# 5_-_MICROCONTROLLER.net
KiCad netlist of a schematic drawn in Altium Designer
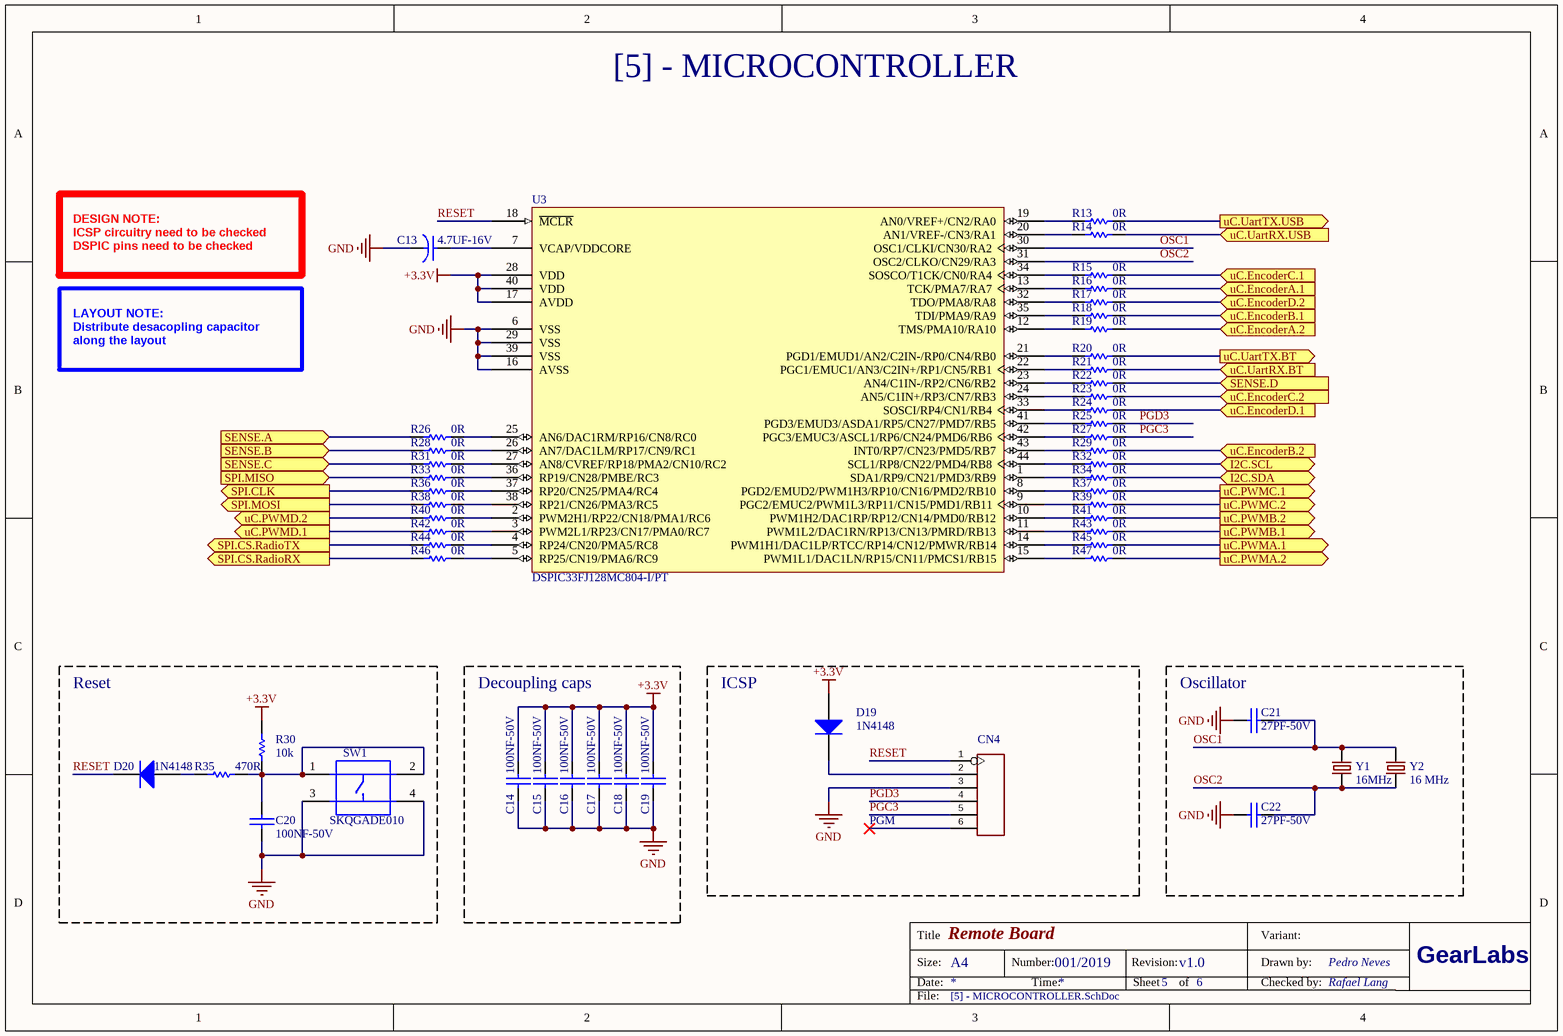
[diagram p0: [5] - MICROCONTROLLER.SchDoc]

(export (version "E")
  (design (tool "Eeschema 10.0.6"))
  (components
    (comp (ref "C13")
      (value "4.7UF-16V")
      (footprint "AVX-A")
      (fields (field (name "MPN") "TAJA475*016#NJ") (field (name "Comment") "302020006"))
      (libsource (lib "Seeed-Capacitor") (part "TANTALUM-SMD-4.7UF-16V(AVX-A)"))
    )
    (comp (ref "C14")
      (value "100NF-50V")
      (footprint "C0603")
      (fields (field (name "MPN") "CC0603KRX7R9BB104") (field (name "Comment") "302010138"))
      (libsource (lib "Seeed-Capacitor") (part "CERAMIC-100NF-50V-10%-X7R(0603)"))
    )
    (comp (ref "C15")
      (value "100NF-50V")
      (footprint "C0603")
      (fields (field (name "MPN") "CC0603KRX7R9BB104") (field (name "Comment") "302010138"))
      (libsource (lib "Seeed-Capacitor") (part "CERAMIC-100NF-50V-10%-X7R(0603)"))
    )
    (comp (ref "C16")
      (value "100NF-50V")
      (footprint "C0603")
      (fields (field (name "MPN") "CC0603KRX7R9BB104") (field (name "Comment") "302010138"))
      (libsource (lib "Seeed-Capacitor") (part "CERAMIC-100NF-50V-10%-X7R(0603)"))
    )
    (comp (ref "C17")
      (value "100NF-50V")
      (footprint "C0603")
      (fields (field (name "MPN") "CC0603KRX7R9BB104") (field (name "Comment") "302010138"))
      (libsource (lib "Seeed-Capacitor") (part "CERAMIC-100NF-50V-10%-X7R(0603)"))
    )
    (comp (ref "C18")
      (value "100NF-50V")
      (footprint "C0603")
      (fields (field (name "MPN") "CC0603KRX7R9BB104") (field (name "Comment") "302010138"))
      (libsource (lib "Seeed-Capacitor") (part "CERAMIC-100NF-50V-10%-X7R(0603)"))
    )
    (comp (ref "C19")
      (value "100NF-50V")
      (footprint "C0603")
      (fields (field (name "MPN") "CC0603KRX7R9BB104") (field (name "Comment") "302010138"))
      (libsource (lib "Seeed-Capacitor") (part "CERAMIC-100NF-50V-10%-X7R(0603)"))
    )
    (comp (ref "C20")
      (value "100NF-50V")
      (footprint "C0603")
      (fields (field (name "MPN") "CC0603KRX7R9BB104") (field (name "Comment") "302010138"))
      (libsource (lib "Seeed-Capacitor") (part "CERAMIC-100NF-50V-10%-X7R(0603)"))
    )
    (comp (ref "C21")
      (value "27PF-50V")
      (footprint "C0603")
      (fields (field (name "MPN") "CC0603JRNPO9BN270") (field (name "Comment") "302010142"))
      (libsource (lib "Seeed-Capacitor") (part "CERAMIC-27PF-50V-5%-NPO(0603)"))
    )
    (comp (ref "C22")
      (value "27PF-50V")
      (footprint "C0603")
      (fields (field (name "MPN") "CC0603JRNPO9BN270") (field (name "Comment") "302010142"))
      (libsource (lib "Seeed-Capacitor") (part "CERAMIC-27PF-50V-5%-NPO(0603)"))
    )
    (comp (ref "CN4")
      (value "320030060")
      (footprint "H6-2.54")
      (fields (field (name "MPN") "F185-1106A1BSYC1"))
      (libsource (lib "Seeed-Connector") (part "DIP-BLACK-FEMALE-HEADER-VERT(6P-2.54)"))
    )
    (comp (ref "D19")
      (value "304040016")
      (footprint "LL-34")
      (fields (field (name "MPN") "1N4148"))
      (libsource (lib "Seeed-Diode") (part "SMD-DIODE-SWITCH-1N4148(LL-34)"))
    )
    (comp (ref "D20")
      (value "304040016")
      (footprint "LL-34")
      (fields (field (name "MPN") "1N4148"))
      (libsource (lib "Seeed-Diode") (part "SMD-DIODE-SWITCH-1N4148(LL-34)"))
    )
    (comp (ref "R13")
      (value "0R")
      (footprint "R0603")
      (fields (field (name "MPN") "RC0603JR-070RL") (field (name "Comment") "301010292"))
      (libsource (lib "Seeed-Resistor") (part "SMD-RES-0R-5%-1/10W(0603)"))
    )
    (comp (ref "R14")
      (value "0R")
      (footprint "R0603")
      (fields (field (name "MPN") "RC0603JR-070RL") (field (name "Comment") "301010292"))
      (libsource (lib "Seeed-Resistor") (part "SMD-RES-0R-5%-1/10W(0603)"))
    )
    (comp (ref "R15")
      (value "0R")
      (footprint "R0603")
      (fields (field (name "MPN") "RC0603JR-070RL") (field (name "Comment") "301010292"))
      (libsource (lib "Seeed-Resistor") (part "SMD-RES-0R-5%-1/10W(0603)"))
    )
    (comp (ref "R16")
      (value "0R")
      (footprint "R0603")
      (fields (field (name "MPN") "RC0603JR-070RL") (field (name "Comment") "301010292"))
      (libsource (lib "Seeed-Resistor") (part "SMD-RES-0R-5%-1/10W(0603)"))
    )
    (comp (ref "R17")
      (value "0R")
      (footprint "R0603")
      (fields (field (name "MPN") "RC0603JR-070RL") (field (name "Comment") "301010292"))
      (libsource (lib "Seeed-Resistor") (part "SMD-RES-0R-5%-1/10W(0603)"))
    )
    (comp (ref "R18")
      (value "0R")
      (footprint "R0603")
      (fields (field (name "MPN") "RC0603JR-070RL") (field (name "Comment") "301010292"))
      (libsource (lib "Seeed-Resistor") (part "SMD-RES-0R-5%-1/10W(0603)"))
    )
    (comp (ref "R19")
      (value "0R")
      (footprint "R0603")
      (fields (field (name "MPN") "RC0603JR-070RL") (field (name "Comment") "301010292"))
      (libsource (lib "Seeed-Resistor") (part "SMD-RES-0R-5%-1/10W(0603)"))
    )
    (comp (ref "R20")
      (value "0R")
      (footprint "R0603")
      (fields (field (name "MPN") "RC0603JR-070RL") (field (name "Comment") "301010292"))
      (libsource (lib "Seeed-Resistor") (part "SMD-RES-0R-5%-1/10W(0603)"))
    )
    (comp (ref "R21")
      (value "0R")
      (footprint "R0603")
      (fields (field (name "MPN") "RC0603JR-070RL") (field (name "Comment") "301010292"))
      (libsource (lib "Seeed-Resistor") (part "SMD-RES-0R-5%-1/10W(0603)"))
    )
    (comp (ref "R22")
      (value "0R")
      (footprint "R0603")
      (fields (field (name "MPN") "RC0603JR-070RL") (field (name "Comment") "301010292"))
      (libsource (lib "Seeed-Resistor") (part "SMD-RES-0R-5%-1/10W(0603)"))
    )
    (comp (ref "R23")
      (value "0R")
      (footprint "R0603")
      (fields (field (name "MPN") "RC0603JR-070RL") (field (name "Comment") "301010292"))
      (libsource (lib "Seeed-Resistor") (part "SMD-RES-0R-5%-1/10W(0603)"))
    )
    (comp (ref "R24")
      (value "0R")
      (footprint "R0603")
      (fields (field (name "MPN") "RC0603JR-070RL") (field (name "Comment") "301010292"))
      (libsource (lib "Seeed-Resistor") (part "SMD-RES-0R-5%-1/10W(0603)"))
    )
    (comp (ref "R25")
      (value "0R")
      (footprint "R0603")
      (fields (field (name "MPN") "RC0603JR-070RL") (field (name "Comment") "301010292"))
      (libsource (lib "Seeed-Resistor") (part "SMD-RES-0R-5%-1/10W(0603)"))
    )
    (comp (ref "R26")
      (value "0R")
      (footprint "R0603")
      (fields (field (name "MPN") "RC0603JR-070RL") (field (name "Comment") "301010292"))
      (libsource (lib "Seeed-Resistor") (part "SMD-RES-0R-5%-1/10W(0603)"))
    )
    (comp (ref "R27")
      (value "0R")
      (footprint "R0603")
      (fields (field (name "MPN") "RC0603JR-070RL") (field (name "Comment") "301010292"))
      (libsource (lib "Seeed-Resistor") (part "SMD-RES-0R-5%-1/10W(0603)"))
    )
    (comp (ref "R28")
      (value "0R")
      (footprint "R0603")
      (fields (field (name "MPN") "RC0603JR-070RL") (field (name "Comment") "301010292"))
      (libsource (lib "Seeed-Resistor") (part "SMD-RES-0R-5%-1/10W(0603)"))
    )
    (comp (ref "R29")
      (value "0R")
      (footprint "R0603")
      (fields (field (name "MPN") "RC0603JR-070RL") (field (name "Comment") "301010292"))
      (libsource (lib "Seeed-Resistor") (part "SMD-RES-0R-5%-1/10W(0603)"))
    )
    (comp (ref "R30")
      (value "10k")
      (footprint "R0603")
      (fields (field (name "MPN") "RC0603FR-0710KL") (field (name "Comment") "301010299"))
      (libsource (lib "Seeed-Resistor") (part "SMD-RES-10K-1%-1/10W(0603)"))
    )
    (comp (ref "R31")
      (value "0R")
      (footprint "R0603")
      (fields (field (name "MPN") "RC0603JR-070RL") (field (name "Comment") "301010292"))
      (libsource (lib "Seeed-Resistor") (part "SMD-RES-0R-5%-1/10W(0603)"))
    )
    (comp (ref "R32")
      (value "0R")
      (footprint "R0603")
      (fields (field (name "MPN") "RC0603JR-070RL") (field (name "Comment") "301010292"))
      (libsource (lib "Seeed-Resistor") (part "SMD-RES-0R-5%-1/10W(0603)"))
    )
    (comp (ref "R33")
      (value "0R")
      (footprint "R0603")
      (fields (field (name "MPN") "RC0603JR-070RL") (field (name "Comment") "301010292"))
      (libsource (lib "Seeed-Resistor") (part "SMD-RES-0R-5%-1/10W(0603)"))
    )
    (comp (ref "R34")
      (value "0R")
      (footprint "R0603")
      (fields (field (name "MPN") "RC0603JR-070RL") (field (name "Comment") "301010292"))
      (libsource (lib "Seeed-Resistor") (part "SMD-RES-0R-5%-1/10W(0603)"))
    )
    (comp (ref "R35")
      (value "470R")
      (footprint "R0603")
      (fields (field (name "MPN") "RC0603JR-07470RL") (field (name "Comment") "301010088"))
      (libsource (lib "Seeed-Resistor") (part "SMD-RES-470R-5%-1/10W(0603)"))
    )
    (comp (ref "R36")
      (value "0R")
      (footprint "R0603")
      (fields (field (name "MPN") "RC0603JR-070RL") (field (name "Comment") "301010292"))
      (libsource (lib "Seeed-Resistor") (part "SMD-RES-0R-5%-1/10W(0603)"))
    )
    (comp (ref "R37")
      (value "0R")
      (footprint "R0603")
      (fields (field (name "MPN") "RC0603JR-070RL") (field (name "Comment") "301010292"))
      (libsource (lib "Seeed-Resistor") (part "SMD-RES-0R-5%-1/10W(0603)"))
    )
    (comp (ref "R38")
      (value "0R")
      (footprint "R0603")
      (fields (field (name "MPN") "RC0603JR-070RL") (field (name "Comment") "301010292"))
      (libsource (lib "Seeed-Resistor") (part "SMD-RES-0R-5%-1/10W(0603)"))
    )
    (comp (ref "R39")
      (value "0R")
      (footprint "R0603")
      (fields (field (name "MPN") "RC0603JR-070RL") (field (name "Comment") "301010292"))
      (libsource (lib "Seeed-Resistor") (part "SMD-RES-0R-5%-1/10W(0603)"))
    )
    (comp (ref "R40")
      (value "0R")
      (footprint "R0603")
      (fields (field (name "MPN") "RC0603JR-070RL") (field (name "Comment") "301010292"))
      (libsource (lib "Seeed-Resistor") (part "SMD-RES-0R-5%-1/10W(0603)"))
    )
    (comp (ref "R41")
      (value "0R")
      (footprint "R0603")
      (fields (field (name "MPN") "RC0603JR-070RL") (field (name "Comment") "301010292"))
      (libsource (lib "Seeed-Resistor") (part "SMD-RES-0R-5%-1/10W(0603)"))
    )
    (comp (ref "R42")
      (value "0R")
      (footprint "R0603")
      (fields (field (name "MPN") "RC0603JR-070RL") (field (name "Comment") "301010292"))
      (libsource (lib "Seeed-Resistor") (part "SMD-RES-0R-5%-1/10W(0603)"))
    )
    (comp (ref "R43")
      (value "0R")
      (footprint "R0603")
      (fields (field (name "MPN") "RC0603JR-070RL") (field (name "Comment") "301010292"))
      (libsource (lib "Seeed-Resistor") (part "SMD-RES-0R-5%-1/10W(0603)"))
    )
    (comp (ref "R44")
      (value "0R")
      (footprint "R0603")
      (fields (field (name "MPN") "RC0603JR-070RL") (field (name "Comment") "301010292"))
      (libsource (lib "Seeed-Resistor") (part "SMD-RES-0R-5%-1/10W(0603)"))
    )
    (comp (ref "R45")
      (value "0R")
      (footprint "R0603")
      (fields (field (name "MPN") "RC0603JR-070RL") (field (name "Comment") "301010292"))
      (libsource (lib "Seeed-Resistor") (part "SMD-RES-0R-5%-1/10W(0603)"))
    )
    (comp (ref "R46")
      (value "0R")
      (footprint "R0603")
      (fields (field (name "MPN") "RC0603JR-070RL") (field (name "Comment") "301010292"))
      (libsource (lib "Seeed-Resistor") (part "SMD-RES-0R-5%-1/10W(0603)"))
    )
    (comp (ref "R47")
      (value "0R")
      (footprint "R0603")
      (fields (field (name "MPN") "RC0603JR-070RL") (field (name "Comment") "301010292"))
      (libsource (lib "Seeed-Resistor") (part "SMD-RES-0R-5%-1/10W(0603)"))
    )
    (comp (ref "SW1")
      (value "311020017")
      (footprint "SW4-SMD-5.2X5.2X1.5MM")
      (fields (field (name "MPN") "SKQGADE010"))
      (libsource (lib "Seeed-Switch") (part "SMD-BUTTON(4P-5.2X5.2X1.5MM-SKQGADE010)-SKQGADE010"))
    )
    (comp (ref "U3")
      (value "DSPIC33FJ128MC804-I/PT")
      (footprint "TQFP-44")
      (description "High-Performance 16-bit Digital Signal Controller, 128 KB Flash, 16 KB RAM, 44-Pin TQFP")
      (libsource (lib "Circuitos Integrados") (part "DSPIC33FJ128MC804-I/PT"))
    )
    (comp (ref "Y1")
      (value "16MHz")
      (footprint "X2-SMD-5.0X3.2X1.3MM")
      (fields (field (name "MPN") "X053201602002") (field (name "Comment") "306010054"))
      (libsource (lib "Seeed-Crystal Oscillator") (part "SMD-CRYSTAL-16MHZ-8PF-20PPM-40R(2P-5.0X3.2MM)"))
    )
    (comp (ref "Y2")
      (value "16 MHz")
      (footprint "HC49US")
      (fields (field (name "MPN") "HC-49US    16.000MHz") (field (name "Comment") "306010014"))
      (libsource (lib "Seeed-Crystal Oscillator") (part "DIP-CRYSTAL-16MHZ-18PF-30PPM-40R(HC49US)"))
    )
  )
  (nets
    (net (code "1") (name "+3.3V") (class "Default")
      (node (ref "C14") (pin "1") (pinfunction "1_1") (pintype "passive"))
      (node (ref "C15") (pin "1") (pinfunction "1_1") (pintype "passive"))
      (node (ref "C16") (pin "1") (pinfunction "1_1") (pintype "passive"))
      (node (ref "C17") (pin "1") (pinfunction "1_1") (pintype "passive"))
      (node (ref "C18") (pin "1") (pinfunction "1_1") (pintype "passive"))
      (node (ref "C19") (pin "1") (pinfunction "1_1") (pintype "passive"))
      (node (ref "D19") (pin "A") (pinfunction "+_A") (pintype "passive"))
      (node (ref "R30") (pin "2") (pinfunction "2_2") (pintype "passive"))
      (node (ref "U3") (pin "17") (pinfunction "AVDD_17") (pintype "power_in"))
      (node (ref "U3") (pin "28") (pinfunction "VDD_28") (pintype "power_in"))
      (node (ref "U3") (pin "40") (pinfunction "VDD_40") (pintype "power_in"))
    )
    (net (code "2") (name "/I2C.SCL") (class "Default")
      (node (ref "R32") (pin "2") (pinfunction "2_2") (pintype "passive"))
    )
    (net (code "3") (name "/I2C.SDA") (class "Default")
      (node (ref "R34") (pin "2") (pinfunction "2_2") (pintype "passive"))
    )
    (net (code "4") (name "/OSC1") (class "Default")
      (node (ref "C21") (pin "1") (pinfunction "1_1") (pintype "passive"))
      (node (ref "U3") (pin "30") (pinfunction "OSC1/CLKI/CN30/RA2_30") (pintype "bidirectional"))
      (node (ref "Y1") (pin "2") (pinfunction "2_2") (pintype "passive"))
      (node (ref "Y2") (pin "2") (pinfunction "2_2") (pintype "passive"))
    )
    (net (code "5") (name "/OSC2") (class "Default")
      (node (ref "C22") (pin "1") (pinfunction "1_1") (pintype "passive"))
      (node (ref "U3") (pin "31") (pinfunction "OSC2/CLKO/CN29/RA3_31") (pintype "bidirectional"))
      (node (ref "Y1") (pin "1") (pinfunction "1_1") (pintype "passive"))
      (node (ref "Y2") (pin "1") (pinfunction "1_1") (pintype "passive"))
    )
    (net (code "6") (name "/PGC3") (class "Default")
      (node (ref "CN4") (pin "5") (pinfunction "5_5") (pintype "passive"))
      (node (ref "R27") (pin "2") (pinfunction "2_2") (pintype "passive"))
    )
    (net (code "7") (name "/PGD3") (class "Default")
      (node (ref "CN4") (pin "4") (pinfunction "4_4") (pintype "passive"))
      (node (ref "R25") (pin "2") (pinfunction "2_2") (pintype "passive"))
    )
    (net (code "8") (name "/RESET") (class "Default")
      (node (ref "CN4") (pin "1") (pinfunction "1_1") (pintype "passive"))
      (node (ref "D20") (pin "C") (pinfunction "-_C") (pintype "passive"))
      (node (ref "U3") (pin "18") (pinfunction "~{MCLR}_18") (pintype "input"))
    )
    (net (code "9") (name "/SENSE.A") (class "Default")
      (node (ref "R26") (pin "1") (pinfunction "1_1") (pintype "passive"))
    )
    (net (code "10") (name "/SENSE.B") (class "Default")
      (node (ref "R28") (pin "1") (pinfunction "1_1") (pintype "passive"))
    )
    (net (code "11") (name "/SENSE.C") (class "Default")
      (node (ref "R31") (pin "1") (pinfunction "1_1") (pintype "passive"))
    )
    (net (code "12") (name "/SENSE.D") (class "Default")
      (node (ref "R22") (pin "2") (pinfunction "2_2") (pintype "passive"))
    )
    (net (code "13") (name "/SPI.CLK") (class "Default")
      (node (ref "R36") (pin "1") (pinfunction "1_1") (pintype "passive"))
    )
    (net (code "14") (name "/SPI.CS.RadioRX") (class "Default")
      (node (ref "R46") (pin "1") (pinfunction "1_1") (pintype "passive"))
    )
    (net (code "15") (name "/SPI.CS.RadioTX") (class "Default")
      (node (ref "R44") (pin "1") (pinfunction "1_1") (pintype "passive"))
    )
    (net (code "16") (name "/SPI.MISO") (class "Default")
      (node (ref "R33") (pin "1") (pinfunction "1_1") (pintype "passive"))
    )
    (net (code "17") (name "/SPI.MOSI") (class "Default")
      (node (ref "R38") (pin "1") (pinfunction "1_1") (pintype "passive"))
    )
    (net (code "18") (name "/uC.EncoderA.1") (class "Default")
      (node (ref "R16") (pin "2") (pinfunction "2_2") (pintype "passive"))
    )
    (net (code "19") (name "/uC.EncoderA.2") (class "Default")
      (node (ref "R19") (pin "2") (pinfunction "2_2") (pintype "passive"))
    )
    (net (code "20") (name "/uC.EncoderB.1") (class "Default")
      (node (ref "R18") (pin "2") (pinfunction "2_2") (pintype "passive"))
    )
    (net (code "21") (name "/uC.EncoderB.2") (class "Default")
      (node (ref "R29") (pin "2") (pinfunction "2_2") (pintype "passive"))
    )
    (net (code "22") (name "/uC.EncoderC.1") (class "Default")
      (node (ref "R15") (pin "2") (pinfunction "2_2") (pintype "passive"))
    )
    (net (code "23") (name "/uC.EncoderC.2") (class "Default")
      (node (ref "R23") (pin "2") (pinfunction "2_2") (pintype "passive"))
    )
    (net (code "24") (name "/uC.EncoderD.1") (class "Default")
      (node (ref "R24") (pin "2") (pinfunction "2_2") (pintype "passive"))
    )
    (net (code "25") (name "/uC.EncoderD.2") (class "Default")
      (node (ref "R17") (pin "2") (pinfunction "2_2") (pintype "passive"))
    )
    (net (code "26") (name "/uC.PWMA.1") (class "Default")
      (node (ref "R45") (pin "2") (pinfunction "2_2") (pintype "passive"))
    )
    (net (code "27") (name "/uC.PWMA.2") (class "Default")
      (node (ref "R47") (pin "2") (pinfunction "2_2") (pintype "passive"))
    )
    (net (code "28") (name "/uC.PWMB.1") (class "Default")
      (node (ref "R43") (pin "2") (pinfunction "2_2") (pintype "passive"))
    )
    (net (code "29") (name "/uC.PWMB.2") (class "Default")
      (node (ref "R41") (pin "2") (pinfunction "2_2") (pintype "passive"))
    )
    (net (code "30") (name "/uC.PWMC.1") (class "Default")
      (node (ref "R37") (pin "2") (pinfunction "2_2") (pintype "passive"))
    )
    (net (code "31") (name "/uC.PWMC.2") (class "Default")
      (node (ref "R39") (pin "2") (pinfunction "2_2") (pintype "passive"))
    )
    (net (code "32") (name "/uC.PWMD.1") (class "Default")
      (node (ref "R42") (pin "1") (pinfunction "1_1") (pintype "passive"))
    )
    (net (code "33") (name "/uC.PWMD.2") (class "Default")
      (node (ref "R40") (pin "1") (pinfunction "1_1") (pintype "passive"))
    )
    (net (code "34") (name "/uC.UartRX.BT") (class "Default")
      (node (ref "R21") (pin "2") (pinfunction "2_2") (pintype "passive"))
    )
    (net (code "35") (name "/uC.UartRX.USB") (class "Default")
      (node (ref "R14") (pin "2") (pinfunction "2_2") (pintype "passive"))
    )
    (net (code "36") (name "/uC.UartTX.BT") (class "Default")
      (node (ref "R20") (pin "2") (pinfunction "2_2") (pintype "passive"))
    )
    (net (code "37") (name "/uC.UartTX.USB") (class "Default")
      (node (ref "R13") (pin "2") (pinfunction "2_2") (pintype "passive"))
    )
    (net (code "38") (name "GND") (class "Default")
      (node (ref "C13") (pin "-") (pinfunction "-_-") (pintype "passive"))
      (node (ref "C14") (pin "2") (pinfunction "2_2") (pintype "passive"))
      (node (ref "C15") (pin "2") (pinfunction "2_2") (pintype "passive"))
      (node (ref "C16") (pin "2") (pinfunction "2_2") (pintype "passive"))
      (node (ref "C17") (pin "2") (pinfunction "2_2") (pintype "passive"))
      (node (ref "C18") (pin "2") (pinfunction "2_2") (pintype "passive"))
      (node (ref "C19") (pin "2") (pinfunction "2_2") (pintype "passive"))
      (node (ref "C20") (pin "2") (pinfunction "2_2") (pintype "passive"))
      (node (ref "C21") (pin "2") (pinfunction "2_2") (pintype "passive"))
      (node (ref "C22") (pin "2") (pinfunction "2_2") (pintype "passive"))
      (node (ref "CN4") (pin "3") (pinfunction "3_3") (pintype "passive"))
      (node (ref "SW1") (pin "3") (pinfunction "B0_3") (pintype "passive"))
      (node (ref "SW1") (pin "4") (pinfunction "B1_4") (pintype "passive"))
      (node (ref "U3") (pin "16") (pinfunction "AVSS_16") (pintype "power_in"))
      (node (ref "U3") (pin "29") (pinfunction "VSS_29") (pintype "power_in"))
      (node (ref "U3") (pin "39") (pinfunction "VSS_39") (pintype "power_in"))
      (node (ref "U3") (pin "6") (pinfunction "VSS_6") (pintype "power_in"))
    )
    (net (code "39") (name "Net-(D19--)") (class "Default")
      (node (ref "CN4") (pin "2") (pinfunction "2_2") (pintype "passive"))
      (node (ref "D19") (pin "C") (pinfunction "-_C") (pintype "passive"))
    )
    (net (code "40") (name "Net-(D20-+)") (class "Default")
      (node (ref "D20") (pin "A") (pinfunction "+_A") (pintype "passive"))
      (node (ref "R35") (pin "1") (pinfunction "1_1") (pintype "passive"))
    )
    (net (code "41") (name "Net-(SW1-A0)") (class "Default")
      (node (ref "C20") (pin "1") (pinfunction "1_1") (pintype "passive"))
      (node (ref "R30") (pin "1") (pinfunction "1_1") (pintype "passive"))
      (node (ref "R35") (pin "2") (pinfunction "2_2") (pintype "passive"))
      (node (ref "SW1") (pin "1") (pinfunction "A0_1") (pintype "passive"))
      (node (ref "SW1") (pin "2") (pinfunction "A1_2") (pintype "passive"))
    )
    (net (code "42") (name "Net-(U3-AN0{slash}VREF+{slash}CN2{slash}RA0)") (class "Default")
      (node (ref "R13") (pin "1") (pinfunction "1_1") (pintype "passive"))
      (node (ref "U3") (pin "19") (pinfunction "AN0/VREF+/CN2/RA0_19") (pintype "bidirectional"))
    )
    (net (code "43") (name "Net-(U3-AN1{slash}VREF-{slash}CN3{slash}RA1)") (class "Default")
      (node (ref "R14") (pin "1") (pinfunction "1_1") (pintype "passive"))
      (node (ref "U3") (pin "20") (pinfunction "AN1/VREF-/CN3/RA1_20") (pintype "bidirectional"))
    )
    (net (code "44") (name "Net-(U3-AN4{slash}C1IN-{slash}RP2{slash}CN6{slash}RB2)") (class "Default")
      (node (ref "R22") (pin "1") (pinfunction "1_1") (pintype "passive"))
      (node (ref "U3") (pin "23") (pinfunction "AN4/C1IN-/RP2/CN6/RB2_23") (pintype "bidirectional"))
    )
    (net (code "45") (name "Net-(U3-AN5{slash}C1IN+{slash}RP3{slash}CN7{slash}RB3)") (class "Default")
      (node (ref "R23") (pin "1") (pinfunction "1_1") (pintype "passive"))
      (node (ref "U3") (pin "24") (pinfunction "AN5/C1IN+/RP3/CN7/RB3_24") (pintype "bidirectional"))
    )
    (net (code "46") (name "Net-(U3-AN6{slash}DAC1RM{slash}RP16{slash}CN8{slash}RC0)") (class "Default")
      (node (ref "R26") (pin "2") (pinfunction "2_2") (pintype "passive"))
      (node (ref "U3") (pin "25") (pinfunction "AN6/DAC1RM/RP16/CN8/RC0_25") (pintype "bidirectional"))
    )
    (net (code "47") (name "Net-(U3-AN7{slash}DAC1LM{slash}RP17{slash}CN9{slash}RC1)") (class "Default")
      (node (ref "R28") (pin "2") (pinfunction "2_2") (pintype "passive"))
      (node (ref "U3") (pin "26") (pinfunction "AN7/DAC1LM/RP17/CN9/RC1_26") (pintype "bidirectional"))
    )
    (net (code "48") (name "Net-(U3-AN8{slash}CVREF{slash}RP18{slash}PMA2{slash}CN10{slash}RC2)") (class "Default")
      (node (ref "R31") (pin "2") (pinfunction "2_2") (pintype "passive"))
      (node (ref "U3") (pin "27") (pinfunction "AN8/CVREF/RP18/PMA2/CN10/RC2_27") (pintype "bidirectional"))
    )
    (net (code "49") (name "Net-(U3-INT0{slash}RP7{slash}CN23{slash}PMD5{slash}RB7)") (class "Default")
      (node (ref "R29") (pin "1") (pinfunction "1_1") (pintype "passive"))
      (node (ref "U3") (pin "43") (pinfunction "INT0/RP7/CN23/PMD5/RB7_43") (pintype "bidirectional"))
    )
    (net (code "50") (name "Net-(U3-PGC1{slash}EMUC1{slash}AN3{slash}C2IN+{slash}RP1{slash}CN5{slash}RB1)") (class "Default")
      (node (ref "R21") (pin "1") (pinfunction "1_1") (pintype "passive"))
      (node (ref "U3") (pin "22") (pinfunction "PGC1/EMUC1/AN3/C2IN+/RP1/CN5/RB1_22") (pintype "bidirectional"))
    )
    (net (code "51") (name "Net-(U3-PGC2{slash}EMUC2{slash}PWM1L3{slash}RP11{slash}CN15{slash}PMD1{slash}RB11)") (class "Default")
      (node (ref "R39") (pin "1") (pinfunction "1_1") (pintype "passive"))
      (node (ref "U3") (pin "9") (pinfunction "PGC2/EMUC2/PWM1L3/RP11/CN15/PMD1/RB11_9") (pintype "bidirectional"))
    )
    (net (code "52") (name "Net-(U3-PGC3{slash}EMUC3{slash}ASCL1{slash}RP6{slash}CN24{slash}PMD6{slash}RB6)") (class "Default")
      (node (ref "R27") (pin "1") (pinfunction "1_1") (pintype "passive"))
      (node (ref "U3") (pin "42") (pinfunction "PGC3/EMUC3/ASCL1/RP6/CN24/PMD6/RB6_42") (pintype "bidirectional"))
    )
    (net (code "53") (name "Net-(U3-PGD1{slash}EMUD1{slash}AN2{slash}C2IN-{slash}RP0{slash}CN4{slash}RB0)") (class "Default")
      (node (ref "R20") (pin "1") (pinfunction "1_1") (pintype "passive"))
      (node (ref "U3") (pin "21") (pinfunction "PGD1/EMUD1/AN2/C2IN-/RP0/CN4/RB0_21") (pintype "bidirectional"))
    )
    (net (code "54") (name "Net-(U3-PGD2{slash}EMUD2{slash}PWM1H3{slash}RP10{slash}CN16{slash}PMD2{slash}RB10)") (class "Default")
      (node (ref "R37") (pin "1") (pinfunction "1_1") (pintype "passive"))
      (node (ref "U3") (pin "8") (pinfunction "PGD2/EMUD2/PWM1H3/RP10/CN16/PMD2/RB10_8") (pintype "bidirectional"))
    )
    (net (code "55") (name "Net-(U3-PGD3{slash}EMUD3{slash}ASDA1{slash}RP5{slash}CN27{slash}PMD7{slash}RB5)") (class "Default")
      (node (ref "R25") (pin "1") (pinfunction "1_1") (pintype "passive"))
      (node (ref "U3") (pin "41") (pinfunction "PGD3/EMUD3/ASDA1/RP5/CN27/PMD7/RB5_41") (pintype "bidirectional"))
    )
    (net (code "56") (name "Net-(U3-PWM1H1{slash}DAC1LP{slash}RTCC{slash}RP14{slash}CN12{slash}PMWR{slash}RB14)") (class "Default")
      (node (ref "R45") (pin "1") (pinfunction "1_1") (pintype "passive"))
      (node (ref "U3") (pin "14") (pinfunction "PWM1H1/DAC1LP/RTCC/RP14/CN12/PMWR/RB14_14") (pintype "bidirectional"))
    )
    (net (code "57") (name "Net-(U3-PWM1H2{slash}DAC1RP{slash}RP12{slash}CN14{slash}PMD0{slash}RB12)") (class "Default")
      (node (ref "R41") (pin "1") (pinfunction "1_1") (pintype "passive"))
      (node (ref "U3") (pin "10") (pinfunction "PWM1H2/DAC1RP/RP12/CN14/PMD0/RB12_10") (pintype "bidirectional"))
    )
    (net (code "58") (name "Net-(U3-PWM1L1{slash}DAC1LN{slash}RP15{slash}CN11{slash}PMCS1{slash}RB15)") (class "Default")
      (node (ref "R47") (pin "1") (pinfunction "1_1") (pintype "passive"))
      (node (ref "U3") (pin "15") (pinfunction "PWM1L1/DAC1LN/RP15/CN11/PMCS1/RB15_15") (pintype "bidirectional"))
    )
    (net (code "59") (name "Net-(U3-PWM1L2{slash}DAC1RN{slash}RP13{slash}CN13{slash}PMRD{slash}RB13)") (class "Default")
      (node (ref "R43") (pin "1") (pinfunction "1_1") (pintype "passive"))
      (node (ref "U3") (pin "11") (pinfunction "PWM1L2/DAC1RN/RP13/CN13/PMRD/RB13_11") (pintype "bidirectional"))
    )
    (net (code "60") (name "Net-(U3-PWM2H1{slash}RP22{slash}CN18{slash}PMA1{slash}RC6)") (class "Default")
      (node (ref "R40") (pin "2") (pinfunction "2_2") (pintype "passive"))
      (node (ref "U3") (pin "2") (pinfunction "PWM2H1/RP22/CN18/PMA1/RC6_2") (pintype "bidirectional"))
    )
    (net (code "61") (name "Net-(U3-PWM2L1{slash}RP23{slash}CN17{slash}PMA0{slash}RC7)") (class "Default")
      (node (ref "R42") (pin "2") (pinfunction "2_2") (pintype "passive"))
      (node (ref "U3") (pin "3") (pinfunction "PWM2L1/RP23/CN17/PMA0/RC7_3") (pintype "bidirectional"))
    )
    (net (code "62") (name "Net-(U3-RP19{slash}CN28{slash}PMBE{slash}RC3)") (class "Default")
      (node (ref "R33") (pin "2") (pinfunction "2_2") (pintype "passive"))
      (node (ref "U3") (pin "36") (pinfunction "RP19/CN28/PMBE/RC3_36") (pintype "bidirectional"))
    )
    (net (code "63") (name "Net-(U3-RP20{slash}CN25{slash}PMA4{slash}RC4)") (class "Default")
      (node (ref "R36") (pin "2") (pinfunction "2_2") (pintype "passive"))
      (node (ref "U3") (pin "37") (pinfunction "RP20/CN25/PMA4/RC4_37") (pintype "bidirectional"))
    )
    (net (code "64") (name "Net-(U3-RP21{slash}CN26{slash}PMA3{slash}RC5)") (class "Default")
      (node (ref "R38") (pin "2") (pinfunction "2_2") (pintype "passive"))
      (node (ref "U3") (pin "38") (pinfunction "RP21/CN26/PMA3/RC5_38") (pintype "bidirectional"))
    )
    (net (code "65") (name "Net-(U3-RP24{slash}CN20{slash}PMA5{slash}RC8)") (class "Default")
      (node (ref "R44") (pin "2") (pinfunction "2_2") (pintype "passive"))
      (node (ref "U3") (pin "4") (pinfunction "RP24/CN20/PMA5/RC8_4") (pintype "bidirectional"))
    )
    (net (code "66") (name "Net-(U3-RP25{slash}CN19{slash}PMA6{slash}RC9)") (class "Default")
      (node (ref "R46") (pin "2") (pinfunction "2_2") (pintype "passive"))
      (node (ref "U3") (pin "5") (pinfunction "RP25/CN19/PMA6/RC9_5") (pintype "bidirectional"))
    )
    (net (code "67") (name "Net-(U3-SCL1{slash}RP8{slash}CN22{slash}PMD4{slash}RB8)") (class "Default")
      (node (ref "R32") (pin "1") (pinfunction "1_1") (pintype "passive"))
      (node (ref "U3") (pin "44") (pinfunction "SCL1/RP8/CN22/PMD4/RB8_44") (pintype "bidirectional"))
    )
    (net (code "68") (name "Net-(U3-SDA1{slash}RP9{slash}CN21{slash}PMD3{slash}RB9)") (class "Default")
      (node (ref "R34") (pin "1") (pinfunction "1_1") (pintype "passive"))
      (node (ref "U3") (pin "1") (pinfunction "SDA1/RP9/CN21/PMD3/RB9_1") (pintype "bidirectional"))
    )
    (net (code "69") (name "Net-(U3-SOSCI{slash}RP4{slash}CN1{slash}RB4)") (class "Default")
      (node (ref "R24") (pin "1") (pinfunction "1_1") (pintype "passive"))
      (node (ref "U3") (pin "33") (pinfunction "SOSCI/RP4/CN1/RB4_33") (pintype "bidirectional"))
    )
    (net (code "70") (name "Net-(U3-SOSCO{slash}T1CK{slash}CN0{slash}RA4)") (class "Default")
      (node (ref "R15") (pin "1") (pinfunction "1_1") (pintype "passive"))
      (node (ref "U3") (pin "34") (pinfunction "SOSCO/T1CK/CN0/RA4_34") (pintype "bidirectional"))
    )
    (net (code "71") (name "Net-(U3-TCK{slash}PMA7{slash}RA7)") (class "Default")
      (node (ref "R16") (pin "1") (pinfunction "1_1") (pintype "passive"))
      (node (ref "U3") (pin "13") (pinfunction "TCK/PMA7/RA7_13") (pintype "bidirectional"))
    )
    (net (code "72") (name "Net-(U3-TDI{slash}PMA9{slash}RA9)") (class "Default")
      (node (ref "R18") (pin "1") (pinfunction "1_1") (pintype "passive"))
      (node (ref "U3") (pin "35") (pinfunction "TDI/PMA9/RA9_35") (pintype "bidirectional"))
    )
    (net (code "73") (name "Net-(U3-TDO{slash}PMA8{slash}RA8)") (class "Default")
      (node (ref "R17") (pin "1") (pinfunction "1_1") (pintype "passive"))
      (node (ref "U3") (pin "32") (pinfunction "TDO/PMA8/RA8_32") (pintype "bidirectional"))
    )
    (net (code "74") (name "Net-(U3-TMS{slash}PMA10{slash}RA10)") (class "Default")
      (node (ref "R19") (pin "1") (pinfunction "1_1") (pintype "passive"))
      (node (ref "U3") (pin "12") (pinfunction "TMS/PMA10/RA10_12") (pintype "bidirectional"))
    )
    (net (code "75") (name "Net-(U3-VCAP{slash}VDDCORE)") (class "Default")
      (node (ref "C13") (pin "+") (pinfunction "+_+") (pintype "passive"))
      (node (ref "U3") (pin "7") (pinfunction "VCAP/VDDCORE_7") (pintype "power_in"))
    )
    (net (code "76") (name "unconnected-(CN4-Pad6)") (class "Default")
      (node (ref "CN4") (pin "6") (pinfunction "6_6") (pintype "passive+no_connect"))
    )
  )
)
